# comparator.net
KiCad netlist of a schematic drawn in EAGLE
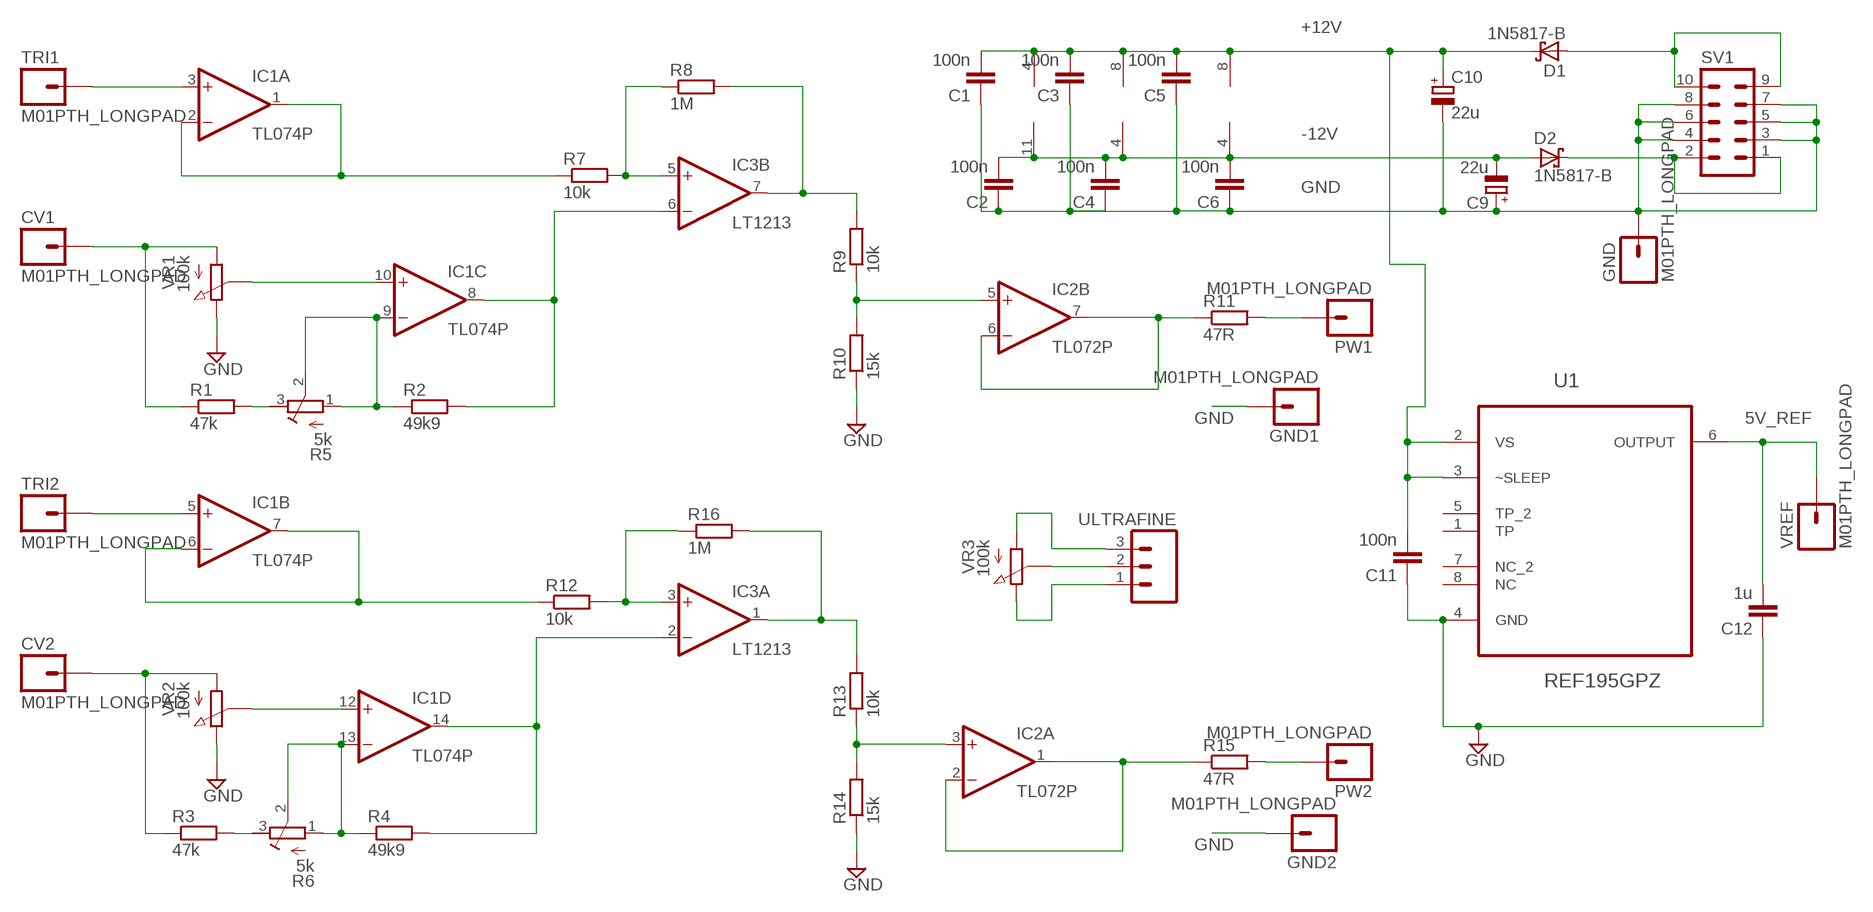
[diagram p0: schematic, sheet 1]

(export (version "E")
  (design (tool "Eeschema 10.0.6"))
  (components
    (comp (ref "C1")
      (value "100n")
      (footprint "eagle-import:C025-025X050")
      (libsource (lib "eagle-import") (part "C-EU025-025X050"))
    )
    (comp (ref "C2")
      (value "100n")
      (footprint "eagle-import:C025-025X050")
      (libsource (lib "eagle-import") (part "C-EU025-025X050"))
    )
    (comp (ref "C3")
      (value "100n")
      (footprint "eagle-import:C025-025X050")
      (libsource (lib "eagle-import") (part "C-EU025-025X050"))
    )
    (comp (ref "C4")
      (value "100n")
      (footprint "eagle-import:C025-025X050")
      (libsource (lib "eagle-import") (part "C-EU025-025X050"))
    )
    (comp (ref "C5")
      (value "100n")
      (footprint "eagle-import:C025-025X050")
      (libsource (lib "eagle-import") (part "C-EU025-025X050"))
    )
    (comp (ref "C6")
      (value "100n")
      (footprint "eagle-import:C025-025X050")
      (libsource (lib "eagle-import") (part "C-EU025-025X050"))
    )
    (comp (ref "C9")
      (value "22u")
      (footprint "eagle-import:E2,5-5")
      (libsource (lib "eagle-import") (part "CPOL-EUE2.5-5"))
    )
    (comp (ref "C10")
      (value "22u")
      (footprint "eagle-import:E2,5-5")
      (libsource (lib "eagle-import") (part "CPOL-EUE2.5-5"))
    )
    (comp (ref "C11")
      (value "100n")
      (footprint "eagle-import:C025-025X050")
      (libsource (lib "eagle-import") (part "C-EU025-025X050"))
    )
    (comp (ref "C12")
      (value "1u")
      (footprint "eagle-import:C050-025X075")
      (libsource (lib "eagle-import") (part "C-EU050-025X075"))
    )
    (comp (ref "CV1")
      (value "M01PTH_LONGPAD")
      (footprint "eagle-import:1X01_LONGPAD")
      (libsource (lib "eagle-import") (part "M01PTH_LONGPAD"))
    )
    (comp (ref "CV2")
      (value "M01PTH_LONGPAD")
      (footprint "eagle-import:1X01_LONGPAD")
      (libsource (lib "eagle-import") (part "M01PTH_LONGPAD"))
    )
    (comp (ref "D1")
      (value "1N5817-B")
      (footprint "eagle-import:DO41-7.6")
      (libsource (lib "eagle-import") (part "1N5817-B"))
    )
    (comp (ref "D2")
      (value "1N5817-B")
      (footprint "eagle-import:DO41-7.6")
      (libsource (lib "eagle-import") (part "1N5817-B"))
    )
    (comp (ref "GND")
      (value "M01PTH_LONGPAD")
      (footprint "eagle-import:1X01_LONGPAD")
      (libsource (lib "eagle-import") (part "M01PTH_LONGPAD"))
    )
    (comp (ref "GND1")
      (value "M01PTH_LONGPAD")
      (footprint "eagle-import:1X01_LONGPAD")
      (libsource (lib "eagle-import") (part "M01PTH_LONGPAD"))
    )
    (comp (ref "GND2")
      (value "M01PTH_LONGPAD")
      (footprint "eagle-import:1X01_LONGPAD")
      (libsource (lib "eagle-import") (part "M01PTH_LONGPAD"))
    )
    (comp (ref "IC1")
      (value "TL074P")
      (footprint "eagle-import:DIL14")
      (libsource (lib "eagle-import") (part "TL074P"))
    )
    (comp (ref "IC2")
      (value "TL072P")
      (footprint "eagle-import:DIL08")
      (libsource (lib "eagle-import") (part "TL072P"))
    )
    (comp (ref "IC3")
      (value "LT1213")
      (footprint "eagle-import:DIL08")
      (libsource (lib "eagle-import") (part "TL072P"))
    )
    (comp (ref "PW1")
      (value "M01PTH_LONGPAD")
      (footprint "eagle-import:1X01_LONGPAD")
      (libsource (lib "eagle-import") (part "M01PTH_LONGPAD"))
    )
    (comp (ref "PW2")
      (value "M01PTH_LONGPAD")
      (footprint "eagle-import:1X01_LONGPAD")
      (libsource (lib "eagle-import") (part "M01PTH_LONGPAD"))
    )
    (comp (ref "R1")
      (value "47k")
      (footprint "eagle-import:02.5-06.8_10")
      (libsource (lib "eagle-import") (part "MULTICOMP_MF25"))
    )
    (comp (ref "R2")
      (value "49k9")
      (footprint "eagle-import:02.5-06.8_10")
      (libsource (lib "eagle-import") (part "MULTICOMP_MF25"))
    )
    (comp (ref "R3")
      (value "47k")
      (footprint "eagle-import:02.5-06.8_10")
      (libsource (lib "eagle-import") (part "MULTICOMP_MF25"))
    )
    (comp (ref "R4")
      (value "49k9")
      (footprint "eagle-import:02.5-06.8_10")
      (libsource (lib "eagle-import") (part "MULTICOMP_MF25"))
    )
    (comp (ref "R5")
      (value "5k")
      (footprint "eagle-import:RTRIM3296W")
      (libsource (lib "eagle-import") (part "R-TRIMM3296W"))
    )
    (comp (ref "R6")
      (value "5k")
      (footprint "eagle-import:RTRIM3296W")
      (libsource (lib "eagle-import") (part "R-TRIMM3296W"))
    )
    (comp (ref "R7")
      (value "10k")
      (footprint "eagle-import:02.5-06.8_10")
      (libsource (lib "eagle-import") (part "MULTICOMP_MF25"))
    )
    (comp (ref "R8")
      (value "1M")
      (footprint "eagle-import:02.5-06.8_10")
      (libsource (lib "eagle-import") (part "MULTICOMP_MF25"))
    )
    (comp (ref "R9")
      (value "10k")
      (footprint "eagle-import:02.5-06.8_10")
      (libsource (lib "eagle-import") (part "MULTICOMP_MF25"))
    )
    (comp (ref "R10")
      (value "15k")
      (footprint "eagle-import:02.5-06.8_10")
      (libsource (lib "eagle-import") (part "MULTICOMP_MF25"))
    )
    (comp (ref "R11")
      (value "47R")
      (footprint "eagle-import:02.5-06.8_10")
      (libsource (lib "eagle-import") (part "MULTICOMP_MF25"))
    )
    (comp (ref "R12")
      (value "10k")
      (footprint "eagle-import:02.5-06.8_10")
      (libsource (lib "eagle-import") (part "MULTICOMP_MF25"))
    )
    (comp (ref "R13")
      (value "10k")
      (footprint "eagle-import:02.5-06.8_10")
      (libsource (lib "eagle-import") (part "MULTICOMP_MF25"))
    )
    (comp (ref "R14")
      (value "15k")
      (footprint "eagle-import:02.5-06.8_10")
      (libsource (lib "eagle-import") (part "MULTICOMP_MF25"))
    )
    (comp (ref "R15")
      (value "47R")
      (footprint "eagle-import:02.5-06.8_10")
      (libsource (lib "eagle-import") (part "MULTICOMP_MF25"))
    )
    (comp (ref "R16")
      (value "1M")
      (footprint "eagle-import:02.5-06.8_10")
      (libsource (lib "eagle-import") (part "MULTICOMP_MF25"))
    )
    (comp (ref "SV1")
      (value "10_PIN_HEADER")
      (footprint "eagle-import:MA05-2")
      (libsource (lib "eagle-import") (part "10_PIN_HEADER"))
    )
    (comp (ref "TRI1")
      (value "M01PTH_LONGPAD")
      (footprint "eagle-import:1X01_LONGPAD")
      (libsource (lib "eagle-import") (part "M01PTH_LONGPAD"))
    )
    (comp (ref "TRI2")
      (value "M01PTH_LONGPAD")
      (footprint "eagle-import:1X01_LONGPAD")
      (libsource (lib "eagle-import") (part "M01PTH_LONGPAD"))
    )
    (comp (ref "U1")
      (value "REF195GPZ")
      (footprint "eagle-import:DIP254P762X533-8")
      (libsource (lib "eagle-import") (part "REF195GPZ"))
    )
    (comp (ref "ULTRAFINE")
      (value "M03LOCK")
      (footprint "eagle-import:1X03_LOCK")
      (libsource (lib "eagle-import") (part "M03LOCK"))
    )
    (comp (ref "VR1")
      (value "100k")
      (footprint "eagle-import:BI_9MM_SIDE")
      (libsource (lib "eagle-import") (part "BI_P09X"))
    )
    (comp (ref "VR2")
      (value "100k")
      (footprint "eagle-import:BI_9MM_SIDE")
      (libsource (lib "eagle-import") (part "BI_P09X"))
    )
    (comp (ref "VR3")
      (value "100k")
      (footprint "eagle-import:BI_9MM_SIDE")
      (libsource (lib "eagle-import") (part "BI_P09X"))
    )
    (comp (ref "VREF")
      (value "M01PTH_LONGPAD")
      (footprint "eagle-import:1X01_LONGPAD")
      (libsource (lib "eagle-import") (part "M01PTH_LONGPAD"))
    )
  )
  (nets
    (net (code "1") (name "/+12V") (class "Default")
      (node (ref "C1") (pin "2") (pinfunction "2_2") (pintype "passive"))
      (node (ref "C10") (pin "+") (pinfunction "+_+") (pintype "passive"))
      (node (ref "C11") (pin "2") (pinfunction "2_2") (pintype "passive"))
      (node (ref "C3") (pin "2") (pinfunction "2_2") (pintype "passive"))
      (node (ref "C5") (pin "2") (pinfunction "2_2") (pintype "passive"))
      (node (ref "D1") (pin "C") (pinfunction "C_C") (pintype "passive"))
      (node (ref "IC1") (pin "4") (pinfunction "V+_4") (pintype "power_in"))
      (node (ref "IC2") (pin "8") (pinfunction "V+_8") (pintype "power_in"))
      (node (ref "IC3") (pin "8") (pinfunction "V+_8") (pintype "power_in"))
      (node (ref "U1") (pin "2") (pinfunction "VS_2") (pintype "power_in"))
      (node (ref "U1") (pin "3") (pinfunction "~{SLEEP}_3") (pintype "input"))
    )
    (net (code "2") (name "/-12V") (class "Default")
      (node (ref "C2") (pin "2") (pinfunction "2_2") (pintype "passive"))
      (node (ref "C4") (pin "2") (pinfunction "2_2") (pintype "passive"))
      (node (ref "C6") (pin "2") (pinfunction "2_2") (pintype "passive"))
      (node (ref "C9") (pin "-") (pinfunction "-_-") (pintype "passive"))
      (node (ref "D2") (pin "A") (pinfunction "A_A") (pintype "passive"))
      (node (ref "IC1") (pin "11") (pinfunction "V-_11") (pintype "power_in"))
      (node (ref "IC2") (pin "4") (pinfunction "V-_4") (pintype "power_in"))
      (node (ref "IC3") (pin "4") (pinfunction "V-_4") (pintype "power_in"))
    )
    (net (code "3") (name "/5V_REF") (class "Default")
      (node (ref "C12") (pin "2") (pinfunction "2_2") (pintype "passive"))
      (node (ref "U1") (pin "6") (pinfunction "OUTPUT_6") (pintype "output"))
      (node (ref "VREF") (pin "1") (pinfunction "1_1") (pintype "passive"))
    )
    (net (code "4") (name "GND") (class "Default")
      (node (ref "C1") (pin "1") (pinfunction "1_1") (pintype "passive"))
      (node (ref "C10") (pin "-") (pinfunction "-_-") (pintype "passive"))
      (node (ref "C11") (pin "1") (pinfunction "1_1") (pintype "passive"))
      (node (ref "C12") (pin "1") (pinfunction "1_1") (pintype "passive"))
      (node (ref "C2") (pin "1") (pinfunction "1_1") (pintype "passive"))
      (node (ref "C3") (pin "1") (pinfunction "1_1") (pintype "passive"))
      (node (ref "C4") (pin "1") (pinfunction "1_1") (pintype "passive"))
      (node (ref "C5") (pin "1") (pinfunction "1_1") (pintype "passive"))
      (node (ref "C6") (pin "1") (pinfunction "1_1") (pintype "passive"))
      (node (ref "C9") (pin "+") (pinfunction "+_+") (pintype "passive"))
      (node (ref "GND") (pin "1") (pinfunction "1_1") (pintype "passive"))
      (node (ref "GND1") (pin "1") (pinfunction "1_1") (pintype "passive"))
      (node (ref "GND2") (pin "1") (pinfunction "1_1") (pintype "passive"))
      (node (ref "R10") (pin "P$1") (pinfunction "1_P$1") (pintype "passive"))
      (node (ref "R14") (pin "P$1") (pinfunction "1_P$1") (pintype "passive"))
      (node (ref "SV1") (pin "3") (pinfunction "3_3") (pintype "passive"))
      (node (ref "SV1") (pin "4") (pinfunction "4_4") (pintype "passive"))
      (node (ref "SV1") (pin "5") (pinfunction "5_5") (pintype "passive"))
      (node (ref "SV1") (pin "6") (pinfunction "6_6") (pintype "passive"))
      (node (ref "SV1") (pin "7") (pinfunction "7_7") (pintype "passive"))
      (node (ref "SV1") (pin "8") (pinfunction "8_8") (pintype "passive"))
      (node (ref "U1") (pin "4") (pinfunction "GND_4") (pintype "passive"))
      (node (ref "VR1") (pin "TOP") (pinfunction "TOP_TOP") (pintype "passive"))
      (node (ref "VR2") (pin "TOP") (pinfunction "TOP_TOP") (pintype "passive"))
    )
    (net (code "5") (name "Net-(D1-PadA)") (class "Default")
      (node (ref "D1") (pin "A") (pinfunction "A_A") (pintype "passive"))
      (node (ref "SV1") (pin "10") (pinfunction "10_10") (pintype "passive"))
      (node (ref "SV1") (pin "9") (pinfunction "9_9") (pintype "passive"))
    )
    (net (code "6") (name "Net-(D2-PadC)") (class "Default")
      (node (ref "D2") (pin "C") (pinfunction "C_C") (pintype "passive"))
      (node (ref "SV1") (pin "1") (pinfunction "1_1") (pintype "passive"))
      (node (ref "SV1") (pin "2") (pinfunction "2_2") (pintype "passive"))
    )
    (net (code "7") (name "Net-(IC1A-+IN)") (class "Default")
      (node (ref "IC1") (pin "3") (pinfunction "+IN_3") (pintype "input"))
      (node (ref "TRI1") (pin "1") (pinfunction "1_1") (pintype "passive"))
    )
    (net (code "8") (name "Net-(IC1A--IN)") (class "Default")
      (node (ref "IC1") (pin "1") (pinfunction "OUT_1") (pintype "output"))
      (node (ref "IC1") (pin "2") (pinfunction "-IN_2") (pintype "input"))
      (node (ref "R7") (pin "P$1") (pinfunction "1_P$1") (pintype "passive"))
    )
    (net (code "9") (name "Net-(IC1B-+IN)") (class "Default")
      (node (ref "IC1") (pin "5") (pinfunction "+IN_5") (pintype "input"))
      (node (ref "TRI2") (pin "1") (pinfunction "1_1") (pintype "passive"))
    )
    (net (code "10") (name "Net-(IC1B--IN)") (class "Default")
      (node (ref "IC1") (pin "6") (pinfunction "-IN_6") (pintype "input"))
      (node (ref "IC1") (pin "7") (pinfunction "OUT_7") (pintype "output"))
      (node (ref "R12") (pin "P$1") (pinfunction "1_P$1") (pintype "passive"))
    )
    (net (code "11") (name "Net-(IC1C-+IN)") (class "Default")
      (node (ref "IC1") (pin "10") (pinfunction "+IN_10") (pintype "input"))
      (node (ref "VR1") (pin "WIPER") (pinfunction "WIPER_WIPER") (pintype "passive"))
    )
    (net (code "12") (name "Net-(IC1C--IN)") (class "Default")
      (node (ref "IC1") (pin "9") (pinfunction "-IN_9") (pintype "input"))
      (node (ref "R2") (pin "P$1") (pinfunction "1_P$1") (pintype "passive"))
      (node (ref "R5") (pin "1") (pinfunction "E_1") (pintype "passive"))
      (node (ref "R5") (pin "2") (pinfunction "S_2") (pintype "passive"))
    )
    (net (code "13") (name "Net-(IC1C-OUT)") (class "Default")
      (node (ref "IC1") (pin "8") (pinfunction "OUT_8") (pintype "output"))
      (node (ref "IC3") (pin "6") (pinfunction "-IN_6") (pintype "input"))
      (node (ref "R2") (pin "P$2") (pinfunction "2_P$2") (pintype "passive"))
    )
    (net (code "14") (name "Net-(IC1D-+IN)") (class "Default")
      (node (ref "IC1") (pin "12") (pinfunction "+IN_12") (pintype "input"))
      (node (ref "VR2") (pin "WIPER") (pinfunction "WIPER_WIPER") (pintype "passive"))
    )
    (net (code "15") (name "Net-(IC1D--IN)") (class "Default")
      (node (ref "IC1") (pin "13") (pinfunction "-IN_13") (pintype "input"))
      (node (ref "R4") (pin "P$1") (pinfunction "1_P$1") (pintype "passive"))
      (node (ref "R6") (pin "1") (pinfunction "E_1") (pintype "passive"))
      (node (ref "R6") (pin "2") (pinfunction "S_2") (pintype "passive"))
    )
    (net (code "16") (name "Net-(IC1D-OUT)") (class "Default")
      (node (ref "IC1") (pin "14") (pinfunction "OUT_14") (pintype "output"))
      (node (ref "IC3") (pin "2") (pinfunction "-IN_2") (pintype "input"))
      (node (ref "R4") (pin "P$2") (pinfunction "2_P$2") (pintype "passive"))
    )
    (net (code "17") (name "Net-(IC2A-+IN)") (class "Default")
      (node (ref "IC2") (pin "3") (pinfunction "+IN_3") (pintype "input"))
      (node (ref "R13") (pin "P$1") (pinfunction "1_P$1") (pintype "passive"))
      (node (ref "R14") (pin "P$2") (pinfunction "2_P$2") (pintype "passive"))
    )
    (net (code "18") (name "Net-(IC2A--IN)") (class "Default")
      (node (ref "IC2") (pin "1") (pinfunction "OUT_1") (pintype "output"))
      (node (ref "IC2") (pin "2") (pinfunction "-IN_2") (pintype "input"))
      (node (ref "R15") (pin "P$1") (pinfunction "1_P$1") (pintype "passive"))
    )
    (net (code "19") (name "Net-(IC2B-+IN)") (class "Default")
      (node (ref "IC2") (pin "5") (pinfunction "+IN_5") (pintype "input"))
      (node (ref "R10") (pin "P$2") (pinfunction "2_P$2") (pintype "passive"))
      (node (ref "R9") (pin "P$1") (pinfunction "1_P$1") (pintype "passive"))
    )
    (net (code "20") (name "Net-(IC2B--IN)") (class "Default")
      (node (ref "IC2") (pin "6") (pinfunction "-IN_6") (pintype "input"))
      (node (ref "IC2") (pin "7") (pinfunction "OUT_7") (pintype "output"))
      (node (ref "R11") (pin "P$1") (pinfunction "1_P$1") (pintype "passive"))
    )
    (net (code "21") (name "Net-(IC3A-+IN)") (class "Default")
      (node (ref "IC3") (pin "3") (pinfunction "+IN_3") (pintype "input"))
      (node (ref "R12") (pin "P$2") (pinfunction "2_P$2") (pintype "passive"))
      (node (ref "R16") (pin "P$1") (pinfunction "1_P$1") (pintype "passive"))
    )
    (net (code "22") (name "Net-(IC3A-OUT)") (class "Default")
      (node (ref "IC3") (pin "1") (pinfunction "OUT_1") (pintype "output"))
      (node (ref "R13") (pin "P$2") (pinfunction "2_P$2") (pintype "passive"))
      (node (ref "R16") (pin "P$2") (pinfunction "2_P$2") (pintype "passive"))
    )
    (net (code "23") (name "Net-(IC3B-+IN)") (class "Default")
      (node (ref "IC3") (pin "5") (pinfunction "+IN_5") (pintype "input"))
      (node (ref "R7") (pin "P$2") (pinfunction "2_P$2") (pintype "passive"))
      (node (ref "R8") (pin "P$1") (pinfunction "1_P$1") (pintype "passive"))
    )
    (net (code "24") (name "Net-(IC3B-OUT)") (class "Default")
      (node (ref "IC3") (pin "7") (pinfunction "OUT_7") (pintype "output"))
      (node (ref "R8") (pin "P$2") (pinfunction "2_P$2") (pintype "passive"))
      (node (ref "R9") (pin "P$2") (pinfunction "2_P$2") (pintype "passive"))
    )
    (net (code "25") (name "Net-(R1-1)") (class "Default")
      (node (ref "CV1") (pin "1") (pinfunction "1_1") (pintype "passive"))
      (node (ref "R1") (pin "P$1") (pinfunction "1_P$1") (pintype "passive"))
      (node (ref "VR1") (pin "BOTTOM") (pinfunction "BOTTOM_BOTTOM") (pintype "passive"))
    )
    (net (code "26") (name "Net-(R1-2)") (class "Default")
      (node (ref "R1") (pin "P$2") (pinfunction "2_P$2") (pintype "passive"))
      (node (ref "R5") (pin "3") (pinfunction "A_3") (pintype "passive"))
    )
    (net (code "27") (name "Net-(R3-1)") (class "Default")
      (node (ref "CV2") (pin "1") (pinfunction "1_1") (pintype "passive"))
      (node (ref "R3") (pin "P$1") (pinfunction "1_P$1") (pintype "passive"))
      (node (ref "VR2") (pin "BOTTOM") (pinfunction "BOTTOM_BOTTOM") (pintype "passive"))
    )
    (net (code "28") (name "Net-(R3-2)") (class "Default")
      (node (ref "R3") (pin "P$2") (pinfunction "2_P$2") (pintype "passive"))
      (node (ref "R6") (pin "3") (pinfunction "A_3") (pintype "passive"))
    )
    (net (code "29") (name "Net-(R11-2)") (class "Default")
      (node (ref "PW1") (pin "1") (pinfunction "1_1") (pintype "passive"))
      (node (ref "R11") (pin "P$2") (pinfunction "2_P$2") (pintype "passive"))
    )
    (net (code "30") (name "Net-(R15-2)") (class "Default")
      (node (ref "PW2") (pin "1") (pinfunction "1_1") (pintype "passive"))
      (node (ref "R15") (pin "P$2") (pinfunction "2_P$2") (pintype "passive"))
    )
    (net (code "31") (name "Net-(ULTRAFINE-Pad1)") (class "Default")
      (node (ref "ULTRAFINE") (pin "1") (pinfunction "1_1") (pintype "passive"))
      (node (ref "VR3") (pin "TOP") (pinfunction "TOP_TOP") (pintype "passive"))
    )
    (net (code "32") (name "Net-(ULTRAFINE-Pad2)") (class "Default")
      (node (ref "ULTRAFINE") (pin "2") (pinfunction "2_2") (pintype "passive"))
      (node (ref "VR3") (pin "WIPER") (pinfunction "WIPER_WIPER") (pintype "passive"))
    )
    (net (code "33") (name "Net-(ULTRAFINE-Pad3)") (class "Default")
      (node (ref "ULTRAFINE") (pin "3") (pinfunction "3_3") (pintype "passive"))
      (node (ref "VR3") (pin "BOTTOM") (pinfunction "BOTTOM_BOTTOM") (pintype "passive"))
    )
    (net (code "34") (name "unconnected-(U1-NC-Pad8)") (class "Default")
      (node (ref "U1") (pin "8") (pinfunction "NC_8") (pintype "no_connect"))
    )
    (net (code "35") (name "unconnected-(U1-NC_2-Pad7)") (class "Default")
      (node (ref "U1") (pin "7") (pinfunction "NC_2_7") (pintype "no_connect"))
    )
    (net (code "36") (name "unconnected-(U1-TP-Pad1)") (class "Default")
      (node (ref "U1") (pin "1") (pinfunction "TP_1") (pintype "passive"))
    )
    (net (code "37") (name "unconnected-(U1-TP_2-Pad5)") (class "Default")
      (node (ref "U1") (pin "5") (pinfunction "TP_2_5") (pintype "passive"))
    )
  )
)
